# zulu_a7_3.net
KiCad netlist of a schematic drawn in Altium Designer
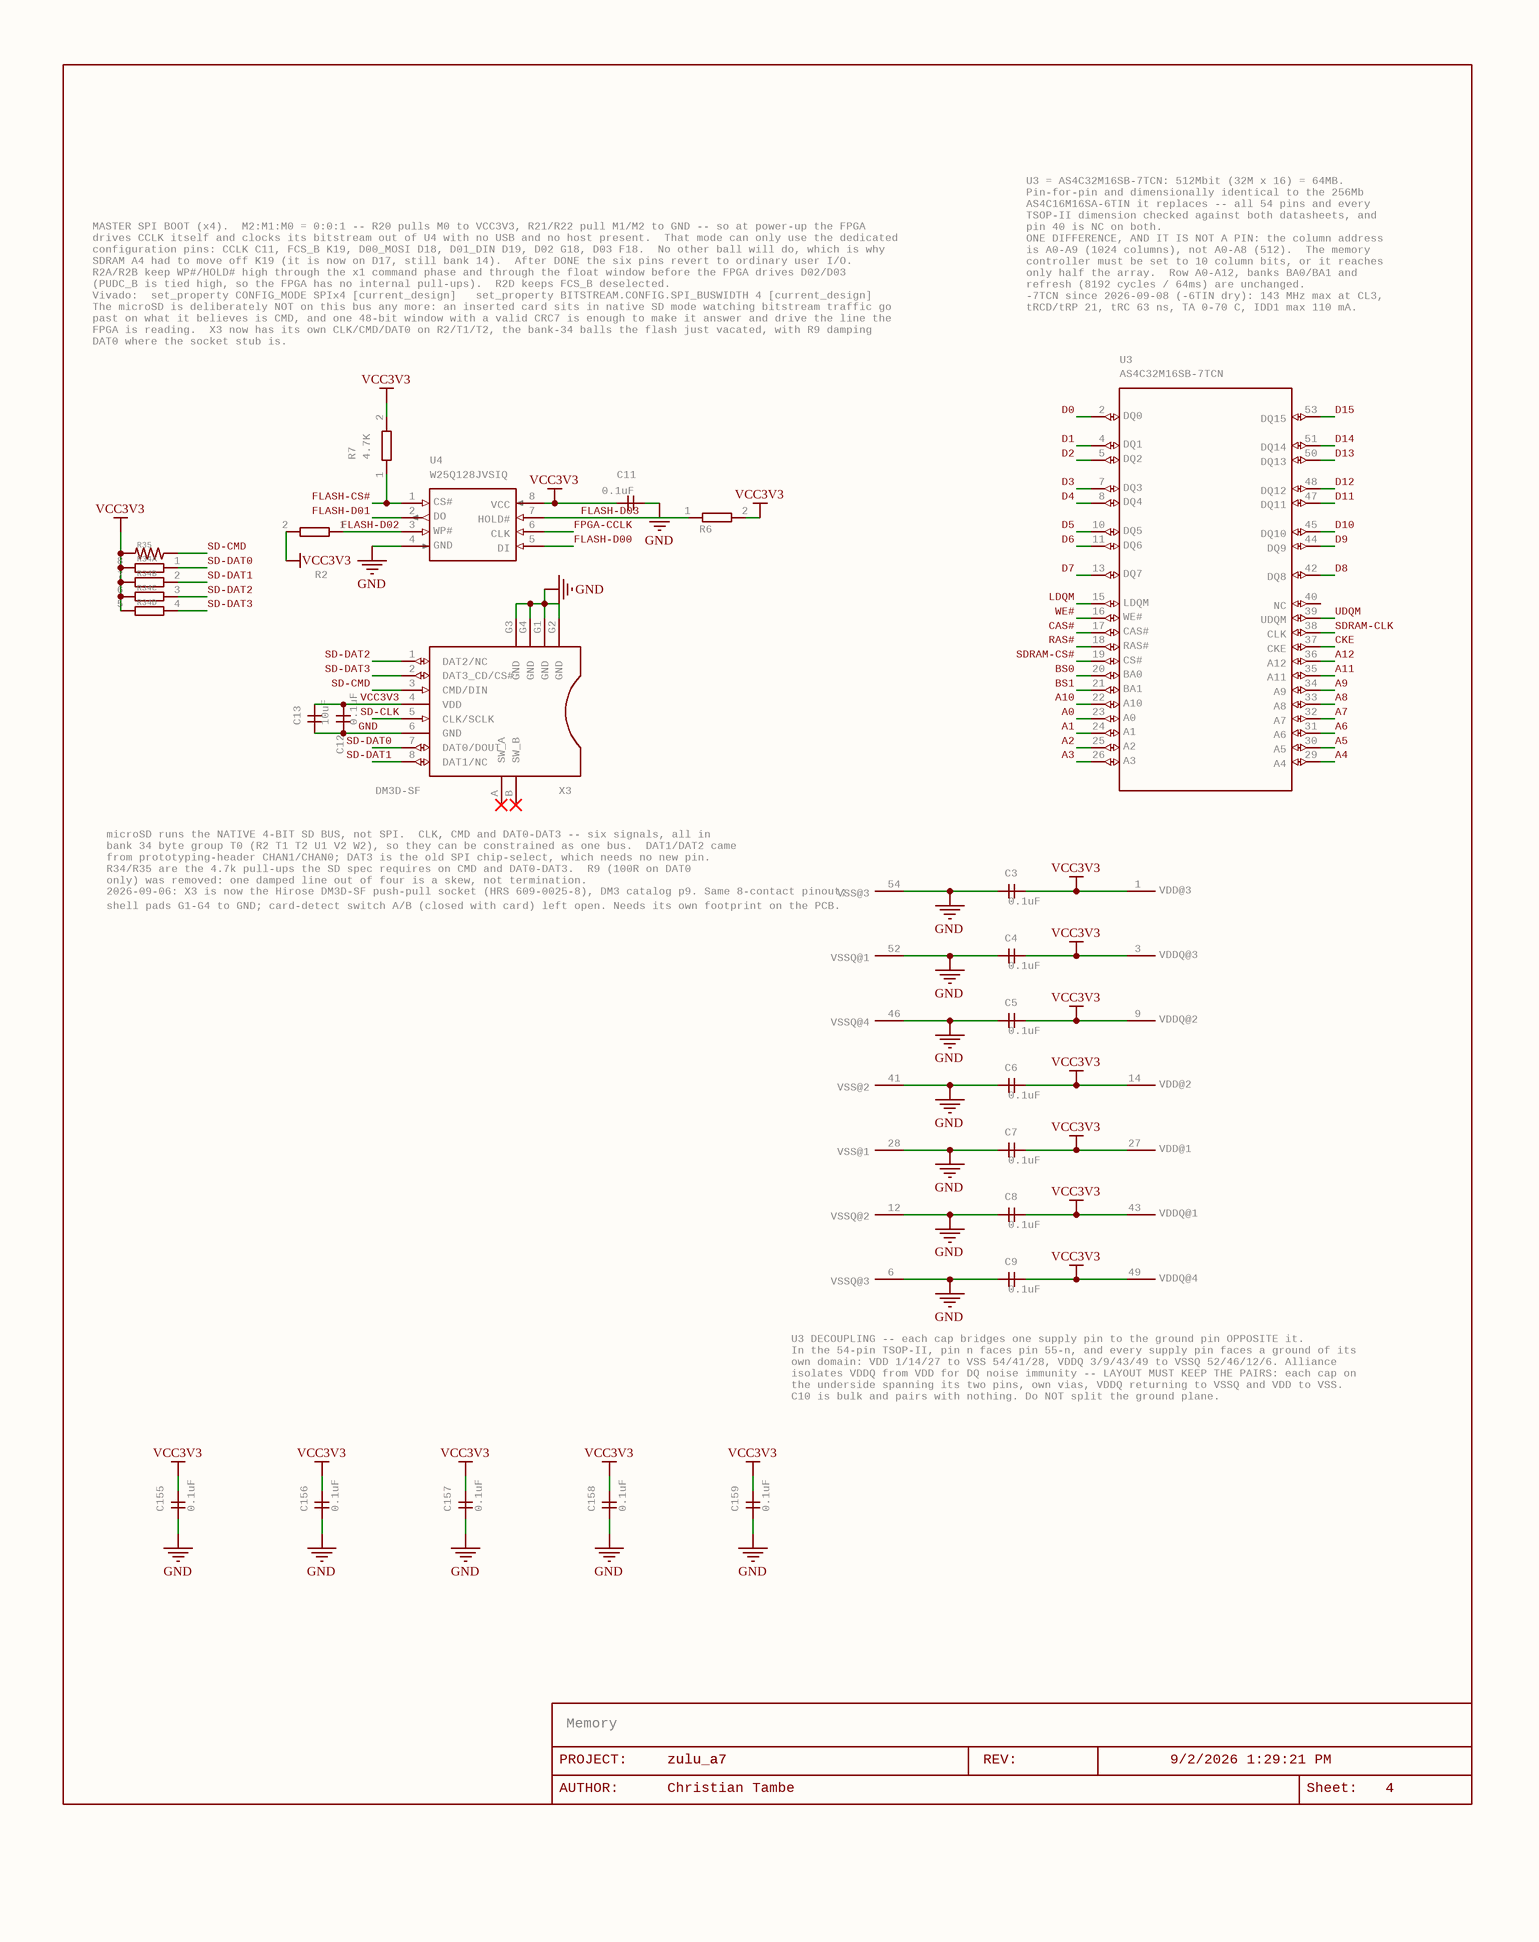
[diagram p0: zulu_a7_3.SchDoc]

(export (version "E")
  (design (tool "Eeschema 10.0.6"))
  (components
    (comp (ref "C3")
      (value "0.1uF")
      (footprint "C0402")
      (description "CAPACITOR, generic non-polarized, horizontal pins")
      (fields (field (name "MANF") "Murata"))
      (libsource (lib "") (part "C-GENERICC0402_1"))
    )
    (comp (ref "C4")
      (value "0.1uF")
      (footprint "C0402")
      (description "CAPACITOR, generic non-polarized, horizontal pins")
      (fields (field (name "MANF") "Murata"))
      (libsource (lib "") (part "C-GENERICC0402_6"))
    )
    (comp (ref "C5")
      (value "0.1uF")
      (footprint "C0402")
      (description "CAPACITOR, generic non-polarized, horizontal pins")
      (fields (field (name "MANF") "Murata"))
      (libsource (lib "rcl") (part "C-GENERICC0402"))
    )
    (comp (ref "C6")
      (value "0.1uF")
      (footprint "C0402")
      (description "CAPACITOR, generic non-polarized, horizontal pins")
      (fields (field (name "MANF") "Murata"))
      (libsource (lib "") (part "C-GENERICC0402_2"))
    )
    (comp (ref "C7")
      (value "0.1uF")
      (footprint "C0402")
      (description "CAPACITOR, generic non-polarized, horizontal pins")
      (fields (field (name "MANF") "Murata"))
      (libsource (lib "") (part "C-GENERICC0402_4"))
    )
    (comp (ref "C8")
      (value "0.1uF")
      (footprint "C0402")
      (description "CAPACITOR, generic non-polarized, horizontal pins")
      (fields (field (name "MANF") "Murata"))
      (libsource (lib "") (part "C-GENERICC0402_5"))
    )
    (comp (ref "C9")
      (value "0.1uF")
      (footprint "C0402")
      (description "CAPACITOR, generic non-polarized, horizontal pins")
      (fields (field (name "MANF") "Murata"))
      (libsource (lib "") (part "C-GENERICC0402_3"))
    )
    (comp (ref "C11")
      (value "0.1uF")
      (footprint "C0402")
      (description "CAPACITOR, generic non-polarized, horizontal pins")
      (fields (field (name "MANF") "Murata"))
      (libsource (lib "") (part "C-GENERICC0402_3"))
    )
    (comp (ref "C12")
      (value "0.1uF")
      (footprint "C0402")
      (description "CAPACITOR, generic non-polarized, horizontal pins")
      (fields (field (name "MANF") "Murata"))
      (libsource (lib "") (part "C-GENERICC0402_3"))
    )
    (comp (ref "C13")
      (value "10uF")
      (footprint "C0603")
      (description "CAPACITOR, generic non-polarized, horizontal pins")
      (fields (field (name "MANF") "Murata"))
      (libsource (lib "rcl") (part "C-GENERICC0603"))
    )
    (comp (ref "C155")
      (value "0.1uF")
      (footprint "C0201")
      (description "CAPACITOR, generic non-polarized, horizontal pins")
      (fields (field (name "MANF") "Murata"))
      (libsource (lib "rcl") (part "C-GENERICC0201"))
    )
    (comp (ref "C156")
      (value "0.1uF")
      (footprint "C0201")
      (description "CAPACITOR, generic non-polarized, horizontal pins")
      (fields (field (name "MANF") "Murata"))
      (libsource (lib "rcl") (part "C-GENERICC0201"))
    )
    (comp (ref "C157")
      (value "0.1uF")
      (footprint "C0201")
      (description "CAPACITOR, generic non-polarized, horizontal pins")
      (fields (field (name "MANF") "Murata"))
      (libsource (lib "rcl") (part "C-GENERICC0201"))
    )
    (comp (ref "C158")
      (value "0.1uF")
      (footprint "C0201")
      (description "CAPACITOR, generic non-polarized, horizontal pins")
      (fields (field (name "MANF") "Murata"))
      (libsource (lib "rcl") (part "C-GENERICC0201"))
    )
    (comp (ref "C159")
      (value "0.1uF")
      (footprint "C0201")
      (description "CAPACITOR, generic non-polarized, horizontal pins")
      (fields (field (name "MANF") "Murata"))
      (libsource (lib "rcl") (part "C-GENERICC0201"))
    )
    (comp (ref "FRAME7")
      (value "DOCFIELD")
      (description "DOCUMENT FIELD")
      (fields
        (field (name "LAST_DATE_TIME") "9/2/2026 1:29:21 PM")
        (field (name "SHEET") "Sheet:")
        (field (name "SHEET_1") "4")
        (field (name "REV") "REV:")
        (field (name "PROJECT") "PROJECT:")
        (field (name "DRAWING_NAME") "zulu_a7")
        (field (name "AUTHOR") "Christian Tambe")
        (field (name "DRAWING_NAME_1") "zulu_a7")
        (field (name "SHEET_2") "4")
        (field (name "LIBRARYNAME") "ctambe")
      )
      (libsource (lib "ctambe") (part "DOCFIELD"))
    )
    (comp (ref "R2")
      (value "4.7K")
      (footprint "R0201")
      (fields (field (name "MANF") "Yageo"))
      (libsource (lib "rcl") (part "R-WIDER0201"))
    )
    (comp (ref "R6")
      (value "4.7K")
      (footprint "R0201")
      (fields (field (name "MANF") "Yageo"))
      (libsource (lib "rcl") (part "R-WIDER0201"))
    )
    (comp (ref "R7")
      (value "4.7K")
      (footprint "R0201")
      (fields (field (name "MANF") "Yageo"))
      (libsource (lib "rcl") (part "R-WIDER0201"))
    )
    (comp (ref "R34")
      (value "4.7K")
      (footprint "742C083")
      (description "Resistor 4-pack   Package of four resistors.")
      (fields (field (name "MANF") "CTS") (field (name "LIBRARYNAME") "ctambe"))
      (libsource (lib "ctambe") (part "RES4742"))
    )
    (comp (ref "R35")
      (value "4.7K")
      (footprint "R0402")
      (description "RESISTOR, American symbol")
      (fields (field (name "MANF") "Yageo"))
      (libsource (lib "rcl") (part "R-US_R0402"))
    )
    (comp (ref "U3")
      (value "AS4C32M16SB-7TCN")
      (footprint "TSOPII-54")
      (fields
        (field (name "GATE") "VDD@3")
        (field (name "MANF") "Alliance Memory")
        (field (name "PART") "U3")
        (field (name "LIBRARYNAME") "ctambe")
      )
      (libsource (lib "") (part "SDRAM-X16-ALLIANCE-512M_1"))
    )
    (comp (ref "U4")
      (value "W25Q128JVSIQ")
      (footprint "SOIC-8_208MIL")
      (description "SPI Flash")
      (fields
        (field (name "GATE") "WP#")
        (field (name "MANF") "Winbond")
        (field (name "PART") "U4")
        (field (name "LIBRARYNAME") "ctambe")
      )
      (libsource (lib "ctambe") (part "SPI_FLASH-SOIC_150_208"))
    )
    (comp (ref "X3")
      (value "DM3D-SF")
      (footprint "DM3D-SF")
      (description "microSD socket, push-pull, Hirose DM3D-SF")
      (fields (field (name "MANF") "Hirose") (field (name "LIBRARYNAME") "ctambe"))
      (libsource (lib "ctambe") (part "MICROSD_CONDM3D-SF"))
    )
  )
  (nets
    (net (code "1") (name "/A0") (class "Default")
      (node (ref "U3") (pin "23") (pinfunction "P$1_23") (pintype "bidirectional"))
    )
    (net (code "2") (name "/A1") (class "Default")
      (node (ref "U3") (pin "24") (pinfunction "P$1_24") (pintype "bidirectional"))
    )
    (net (code "3") (name "/A2") (class "Default")
      (node (ref "U3") (pin "25") (pinfunction "P$1_25") (pintype "bidirectional"))
    )
    (net (code "4") (name "/A3") (class "Default")
      (node (ref "U3") (pin "26") (pinfunction "P$1_26") (pintype "bidirectional"))
    )
    (net (code "5") (name "/A4") (class "Default")
      (node (ref "U3") (pin "29") (pinfunction "P$1_29") (pintype "bidirectional"))
    )
    (net (code "6") (name "/A5") (class "Default")
      (node (ref "U3") (pin "30") (pinfunction "P$1_30") (pintype "bidirectional"))
    )
    (net (code "7") (name "/A6") (class "Default")
      (node (ref "U3") (pin "31") (pinfunction "P$1_31") (pintype "bidirectional"))
    )
    (net (code "8") (name "/A7") (class "Default")
      (node (ref "U3") (pin "32") (pinfunction "P$1_32") (pintype "bidirectional"))
    )
    (net (code "9") (name "/A8") (class "Default")
      (node (ref "U3") (pin "33") (pinfunction "P$1_33") (pintype "bidirectional"))
    )
    (net (code "10") (name "/A9") (class "Default")
      (node (ref "U3") (pin "34") (pinfunction "P$1_34") (pintype "bidirectional"))
    )
    (net (code "11") (name "/A10") (class "Default")
      (node (ref "U3") (pin "22") (pinfunction "P$1_22") (pintype "bidirectional"))
    )
    (net (code "12") (name "/A11") (class "Default")
      (node (ref "U3") (pin "35") (pinfunction "P$1_35") (pintype "bidirectional"))
    )
    (net (code "13") (name "/A12") (class "Default")
      (node (ref "U3") (pin "36") (pinfunction "P$1_36") (pintype "bidirectional"))
    )
    (net (code "14") (name "/BS0") (class "Default")
      (node (ref "U3") (pin "20") (pinfunction "P$1_20") (pintype "bidirectional"))
    )
    (net (code "15") (name "/BS1") (class "Default")
      (node (ref "U3") (pin "21") (pinfunction "P$1_21") (pintype "bidirectional"))
    )
    (net (code "16") (name "/CAS#") (class "Default")
      (node (ref "U3") (pin "17") (pinfunction "P$1_17") (pintype "bidirectional"))
    )
    (net (code "17") (name "/CKE") (class "Default")
      (node (ref "U3") (pin "37") (pinfunction "P$1_37") (pintype "bidirectional"))
    )
    (net (code "18") (name "/D0") (class "Default")
      (node (ref "U3") (pin "2") (pinfunction "P$1_2") (pintype "bidirectional"))
    )
    (net (code "19") (name "/D1") (class "Default")
      (node (ref "U3") (pin "4") (pinfunction "P$1_4") (pintype "bidirectional"))
    )
    (net (code "20") (name "/D2") (class "Default")
      (node (ref "U3") (pin "5") (pinfunction "P$1_5") (pintype "bidirectional"))
    )
    (net (code "21") (name "/D3") (class "Default")
      (node (ref "U3") (pin "7") (pinfunction "P$1_7") (pintype "bidirectional"))
    )
    (net (code "22") (name "/D4") (class "Default")
      (node (ref "U3") (pin "8") (pinfunction "P$1_8") (pintype "bidirectional"))
    )
    (net (code "23") (name "/D5") (class "Default")
      (node (ref "U3") (pin "10") (pinfunction "P$1_10") (pintype "bidirectional"))
    )
    (net (code "24") (name "/D6") (class "Default")
      (node (ref "U3") (pin "11") (pinfunction "P$1_11") (pintype "bidirectional"))
    )
    (net (code "25") (name "/D7") (class "Default")
      (node (ref "U3") (pin "13") (pinfunction "P$1_13") (pintype "bidirectional"))
    )
    (net (code "26") (name "/D8") (class "Default")
      (node (ref "U3") (pin "42") (pinfunction "P$1_42") (pintype "bidirectional"))
    )
    (net (code "27") (name "/D9") (class "Default")
      (node (ref "U3") (pin "44") (pinfunction "P$1_44") (pintype "bidirectional"))
    )
    (net (code "28") (name "/D10") (class "Default")
      (node (ref "U3") (pin "45") (pinfunction "P$1_45") (pintype "bidirectional"))
    )
    (net (code "29") (name "/D11") (class "Default")
      (node (ref "U3") (pin "47") (pinfunction "P$1_47") (pintype "bidirectional"))
    )
    (net (code "30") (name "/D12") (class "Default")
      (node (ref "U3") (pin "48") (pinfunction "P$1_48") (pintype "bidirectional"))
    )
    (net (code "31") (name "/D13") (class "Default")
      (node (ref "U3") (pin "50") (pinfunction "P$1_50") (pintype "bidirectional"))
    )
    (net (code "32") (name "/D14") (class "Default")
      (node (ref "U3") (pin "51") (pinfunction "P$1_51") (pintype "bidirectional"))
    )
    (net (code "33") (name "/D15") (class "Default")
      (node (ref "U3") (pin "53") (pinfunction "P$1_53") (pintype "bidirectional"))
    )
    (net (code "34") (name "/FLASH-CS#") (class "Default")
      (node (ref "R7") (pin "1") (pinfunction "1_1") (pintype "passive"))
      (node (ref "U4") (pin "1") (pinfunction "1_1") (pintype "input"))
    )
    (net (code "35") (name "/FLASH-D00") (class "Default")
      (node (ref "U4") (pin "5") (pinfunction "1_5") (pintype "input"))
    )
    (net (code "36") (name "/FLASH-D01") (class "Default")
      (node (ref "U4") (pin "2") (pinfunction "1_2") (pintype "output"))
    )
    (net (code "37") (name "/FLASH-D02") (class "Default")
      (node (ref "R2") (pin "1") (pinfunction "1_1") (pintype "passive"))
      (node (ref "U4") (pin "3") (pinfunction "1_3") (pintype "input"))
    )
    (net (code "38") (name "/FLASH-D03") (class "Default")
      (node (ref "R6") (pin "1") (pinfunction "1_1") (pintype "passive"))
      (node (ref "U4") (pin "7") (pinfunction "1_7") (pintype "input"))
    )
    (net (code "39") (name "/FPGA-CCLK") (class "Default")
      (node (ref "U4") (pin "6") (pinfunction "1_6") (pintype "input"))
    )
    (net (code "40") (name "/LDQM") (class "Default")
      (node (ref "U3") (pin "15") (pinfunction "P$1_15") (pintype "bidirectional"))
    )
    (net (code "41") (name "/RAS#") (class "Default")
      (node (ref "U3") (pin "18") (pinfunction "P$1_18") (pintype "bidirectional"))
    )
    (net (code "42") (name "/SD-CLK") (class "Default")
      (node (ref "X3") (pin "5") (pinfunction "CLK/SCLK_5") (pintype "input"))
    )
    (net (code "43") (name "/SD-CMD") (class "Default")
      (node (ref "R35") (pin "1") (pinfunction "1_1") (pintype "passive"))
      (node (ref "X3") (pin "3") (pinfunction "CMD/DIN_3") (pintype "input"))
    )
    (net (code "44") (name "/SD-DAT0") (class "Default")
      (node (ref "R34") (pin "1") (pinfunction "1_1") (pintype "passive"))
      (node (ref "X3") (pin "7") (pinfunction "DAT0/DOUT_7") (pintype "bidirectional"))
    )
    (net (code "45") (name "/SD-DAT1") (class "Default")
      (node (ref "R34") (pin "2") (pinfunction "1_2") (pintype "passive"))
      (node (ref "X3") (pin "8") (pinfunction "DAT1/NC_8") (pintype "bidirectional"))
    )
    (net (code "46") (name "/SD-DAT2") (class "Default")
      (node (ref "R34") (pin "3") (pinfunction "1_3") (pintype "passive"))
      (node (ref "X3") (pin "1") (pinfunction "DAT2/NC_1") (pintype "bidirectional"))
    )
    (net (code "47") (name "/SD-DAT3") (class "Default")
      (node (ref "R34") (pin "4") (pinfunction "1_4") (pintype "passive"))
      (node (ref "X3") (pin "2") (pinfunction "DAT3_CD/CS#_2") (pintype "bidirectional"))
    )
    (net (code "48") (name "/SDRAM-CLK") (class "Default")
      (node (ref "U3") (pin "38") (pinfunction "P$1_38") (pintype "bidirectional"))
    )
    (net (code "49") (name "/SDRAM-CS#") (class "Default")
      (node (ref "U3") (pin "19") (pinfunction "P$1_19") (pintype "bidirectional"))
    )
    (net (code "50") (name "/UDQM") (class "Default")
      (node (ref "U3") (pin "39") (pinfunction "P$1_39") (pintype "bidirectional"))
    )
    (net (code "51") (name "/WE#") (class "Default")
      (node (ref "U3") (pin "16") (pinfunction "P$1_16") (pintype "bidirectional"))
    )
    (net (code "52") (name "GND") (class "Default")
      (node (ref "C11") (pin "1") (pinfunction "1_1") (pintype "passive"))
      (node (ref "C12") (pin "1") (pinfunction "1_1") (pintype "passive"))
      (node (ref "C13") (pin "1") (pinfunction "1_1") (pintype "passive"))
      (node (ref "C155") (pin "1") (pinfunction "1_1") (pintype "passive"))
      (node (ref "C156") (pin "1") (pinfunction "1_1") (pintype "passive"))
      (node (ref "C157") (pin "1") (pinfunction "1_1") (pintype "passive"))
      (node (ref "C158") (pin "1") (pinfunction "1_1") (pintype "passive"))
      (node (ref "C159") (pin "1") (pinfunction "1_1") (pintype "passive"))
      (node (ref "C3") (pin "1") (pinfunction "1_1") (pintype "passive"))
      (node (ref "C4") (pin "1") (pinfunction "1_1") (pintype "passive"))
      (node (ref "C5") (pin "1") (pinfunction "1_1") (pintype "passive"))
      (node (ref "C6") (pin "1") (pinfunction "1_1") (pintype "passive"))
      (node (ref "C7") (pin "1") (pinfunction "1_1") (pintype "passive"))
      (node (ref "C8") (pin "1") (pinfunction "1_1") (pintype "passive"))
      (node (ref "C9") (pin "1") (pinfunction "1_1") (pintype "passive"))
      (node (ref "U3") (pin "12") (pinfunction "P$1_12") (pintype "power_in"))
      (node (ref "U3") (pin "28") (pinfunction "P$1_28") (pintype "power_in"))
      (node (ref "U3") (pin "41") (pinfunction "P$1_41") (pintype "power_in"))
      (node (ref "U3") (pin "46") (pinfunction "P$1_46") (pintype "power_in"))
      (node (ref "U3") (pin "52") (pinfunction "P$1_52") (pintype "power_in"))
      (node (ref "U3") (pin "54") (pinfunction "P$1_54") (pintype "power_in"))
      (node (ref "U3") (pin "6") (pinfunction "P$1_6") (pintype "power_in"))
      (node (ref "U4") (pin "4") (pinfunction "1_4") (pintype "input"))
      (node (ref "X3") (pin "6") (pinfunction "GND_6") (pintype "passive"))
      (node (ref "X3") (pin "G1") (pinfunction "GND_G1") (pintype "passive"))
      (node (ref "X3") (pin "G2") (pinfunction "GND_G2") (pintype "passive"))
      (node (ref "X3") (pin "G3") (pinfunction "GND_G3") (pintype "passive"))
      (node (ref "X3") (pin "G4") (pinfunction "GND_G4") (pintype "passive"))
    )
    (net (code "53") (name "VCC3V3") (class "Default")
      (node (ref "C11") (pin "2") (pinfunction "2_2") (pintype "passive"))
      (node (ref "C12") (pin "2") (pinfunction "2_2") (pintype "passive"))
      (node (ref "C13") (pin "2") (pinfunction "2_2") (pintype "passive"))
      (node (ref "C155") (pin "2") (pinfunction "2_2") (pintype "passive"))
      (node (ref "C156") (pin "2") (pinfunction "2_2") (pintype "passive"))
      (node (ref "C157") (pin "2") (pinfunction "2_2") (pintype "passive"))
      (node (ref "C158") (pin "2") (pinfunction "2_2") (pintype "passive"))
      (node (ref "C159") (pin "2") (pinfunction "2_2") (pintype "passive"))
      (node (ref "C3") (pin "2") (pinfunction "2_2") (pintype "passive"))
      (node (ref "C4") (pin "2") (pinfunction "2_2") (pintype "passive"))
      (node (ref "C5") (pin "2") (pinfunction "2_2") (pintype "passive"))
      (node (ref "C6") (pin "2") (pinfunction "2_2") (pintype "passive"))
      (node (ref "C7") (pin "2") (pinfunction "2_2") (pintype "passive"))
      (node (ref "C8") (pin "2") (pinfunction "2_2") (pintype "passive"))
      (node (ref "C9") (pin "2") (pinfunction "2_2") (pintype "passive"))
      (node (ref "R2") (pin "2") (pinfunction "2_2") (pintype "passive"))
      (node (ref "R34") (pin "5") (pinfunction "2_5") (pintype "passive"))
      (node (ref "R34") (pin "6") (pinfunction "2_6") (pintype "passive"))
      (node (ref "R34") (pin "7") (pinfunction "2_7") (pintype "passive"))
      (node (ref "R34") (pin "8") (pinfunction "2_8") (pintype "passive"))
      (node (ref "R35") (pin "2") (pinfunction "2_2") (pintype "passive"))
      (node (ref "R6") (pin "2") (pinfunction "2_2") (pintype "passive"))
      (node (ref "R7") (pin "2") (pinfunction "2_2") (pintype "passive"))
      (node (ref "U3") (pin "1") (pinfunction "P$1_1") (pintype "power_in"))
      (node (ref "U3") (pin "14") (pinfunction "P$1_14") (pintype "power_in"))
      (node (ref "U3") (pin "27") (pinfunction "P$1_27") (pintype "power_in"))
      (node (ref "U3") (pin "3") (pinfunction "P$1_3") (pintype "power_in"))
      (node (ref "U3") (pin "43") (pinfunction "P$1_43") (pintype "power_in"))
      (node (ref "U3") (pin "49") (pinfunction "P$1_49") (pintype "power_in"))
      (node (ref "U3") (pin "9") (pinfunction "P$1_9") (pintype "power_in"))
      (node (ref "U4") (pin "8") (pinfunction "1_8") (pintype "input"))
      (node (ref "X3") (pin "4") (pinfunction "VDD_4") (pintype "passive"))
    )
    (net (code "54") (name "unconnected-(U3AO-P$1-Pad40)") (class "Default")
      (node (ref "U3") (pin "40") (pinfunction "P$1_40") (pintype "bidirectional"))
    )
    (net (code "55") (name "unconnected-(X3-SW_A-PadA)") (class "Default")
      (node (ref "X3") (pin "A") (pinfunction "SW_A_A") (pintype "passive+no_connect"))
    )
    (net (code "56") (name "unconnected-(X3-SW_B-PadB)") (class "Default")
      (node (ref "X3") (pin "B") (pinfunction "SW_B_B") (pintype "passive+no_connect"))
    )
  )
)
